# Gastroscopy-Tool-Interface_Connectors.net
KiCad netlist of a schematic drawn in Altium Designer
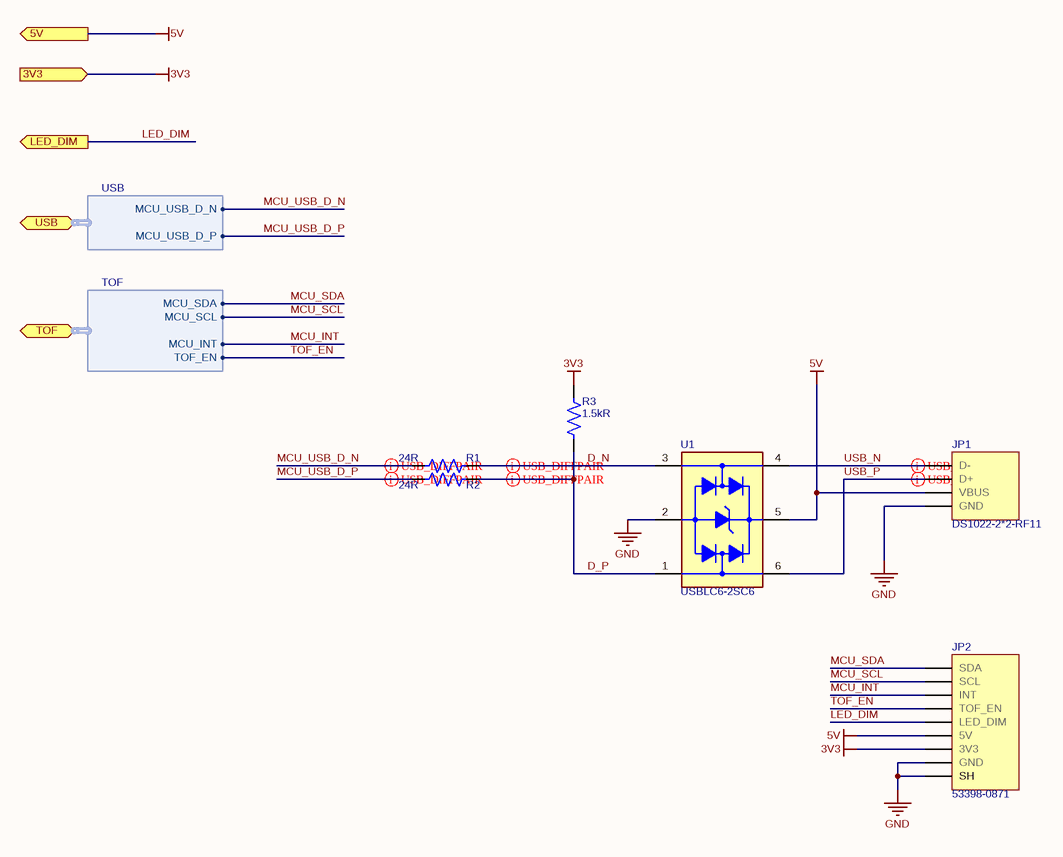
[diagram p0: Gastroscopy-Tool-Interface_Connectors.SchDoc]

(export (version "E")
  (design (tool "Eeschema 10.0.6"))
  (components
    (comp (ref "JP1")
      (value "DS1022-2*2-RF11")
      (footprint "DS1022-2*2-RF11")
      (description "CONN HEADER VERT 2POS 2.54MM")
      (libsource (lib "Gastroscopy-Tool") (part "DS1022-2*2-RF11"))
    )
    (comp (ref "JP2")
      (value "53398-0871")
      (footprint "PICOBLADE_533980871")
      (description "CONN HEADER SMD 8POS 1.25MM")
      (libsource (lib "Gastroscopy-Tool") (part "533980871"))
    )
    (comp (ref "R1")
      (value "24R")
      (footprint "RES_0603")
      (description "RES 24 OHM 1% 1/10W 0603")
      (fields (field (name "TOLERANCE") "1%"))
      (libsource (lib "Industrial-Controller") (part "RC0603FR-0724RL"))
    )
    (comp (ref "R2")
      (value "24R")
      (footprint "RES_0603")
      (description "RES 24 OHM 1% 1/10W 0603")
      (fields (field (name "TOLERANCE") "1%"))
      (libsource (lib "Industrial-Controller") (part "RC0603FR-0724RL"))
    )
    (comp (ref "R3")
      (value "1.5kR")
      (footprint "RES_0603")
      (description "RES 1.5K OHM 1% 1/10W 0603")
      (fields (field (name "TOLERANCE") "1%"))
      (libsource (lib "Industrial-Controller") (part "RC0603FR-071K5L"))
    )
    (comp (ref "U1")
      (value "USBLC6-2SC6")
      (footprint "SOT-23-6")
      (description "TVS DIODE 5.25VWM 17VC SOT23-6")
      (libsource (lib "Industrial-Controller") (part "USBLC6-2SC6"))
    )
  )
  (nets
    (net (code "3") (name "/D_N") (class "Default")
      (node (ref "R1") (pin "2") (pinfunction "2_2") (pintype "passive"))
      (node (ref "U1") (pin "3") (pinfunction "I/O_2_3") (pintype "passive"))
    )
    (net (code "4") (name "/D_P") (class "Default")
      (node (ref "R2") (pin "2") (pinfunction "2_2") (pintype "passive"))
      (node (ref "R3") (pin "2") (pinfunction "2_2") (pintype "passive"))
      (node (ref "U1") (pin "1") (pinfunction "I/O_1_1") (pintype "passive"))
    )
    (net (code "5") (name "/LED_DIM") (class "Default")
      (node (ref "JP2") (pin "5") (pinfunction "5_5") (pintype "passive"))
    )
    (net (code "6") (name "/MCU_INT") (class "Default")
      (node (ref "JP2") (pin "3") (pinfunction "3_3") (pintype "passive"))
    )
    (net (code "7") (name "/MCU_SCL") (class "Default")
      (node (ref "JP2") (pin "2") (pinfunction "2_2") (pintype "passive"))
    )
    (net (code "8") (name "/MCU_SDA") (class "Default")
      (node (ref "JP2") (pin "1") (pinfunction "1_1") (pintype "passive"))
    )
    (net (code "9") (name "/MCU_USB_D_N") (class "Default")
      (node (ref "R1") (pin "1") (pinfunction "1_1") (pintype "passive"))
    )
    (net (code "10") (name "/MCU_USB_D_P") (class "Default")
      (node (ref "R2") (pin "1") (pinfunction "1_1") (pintype "passive"))
    )
    (net (code "11") (name "/TOF_EN") (class "Default")
      (node (ref "JP2") (pin "4") (pinfunction "4_4") (pintype "passive"))
    )
    (net (code "12") (name "/USB_N") (class "Default")
      (node (ref "JP1") (pin "1") (pinfunction "1_1") (pintype "passive"))
      (node (ref "U1") (pin "4") (pinfunction "I/O_3_4") (pintype "passive"))
    )
    (net (code "13") (name "/USB_P") (class "Default")
      (node (ref "JP1") (pin "2") (pinfunction "2_2") (pintype "passive"))
      (node (ref "U1") (pin "6") (pinfunction "I/O_4_6") (pintype "passive"))
    )
    (net (code "16") (name "3V3") (class "Default")
      (node (ref "JP2") (pin "7") (pinfunction "7_7") (pintype "passive"))
      (node (ref "R3") (pin "1") (pinfunction "1_1") (pintype "passive"))
    )
    (net (code "17") (name "5V") (class "Default")
      (node (ref "JP1") (pin "3") (pinfunction "3_3") (pintype "passive"))
      (node (ref "JP2") (pin "6") (pinfunction "6_6") (pintype "passive"))
      (node (ref "U1") (pin "5") (pinfunction "VBUS_5") (pintype "passive"))
    )
    (net (code "18") (name "GND") (class "Default")
      (node (ref "JP1") (pin "4") (pinfunction "4_4") (pintype "passive"))
      (node (ref "JP2") (pin "8") (pinfunction "8_8") (pintype "passive"))
      (node (ref "JP2") (pin "SH") (pinfunction "SH_SH") (pintype "passive"))
      (node (ref "U1") (pin "2") (pinfunction "GND_2") (pintype "passive"))
    )
  )
)
